# hr_subsystem.net
KiCad netlist of a schematic drawn in EAGLE
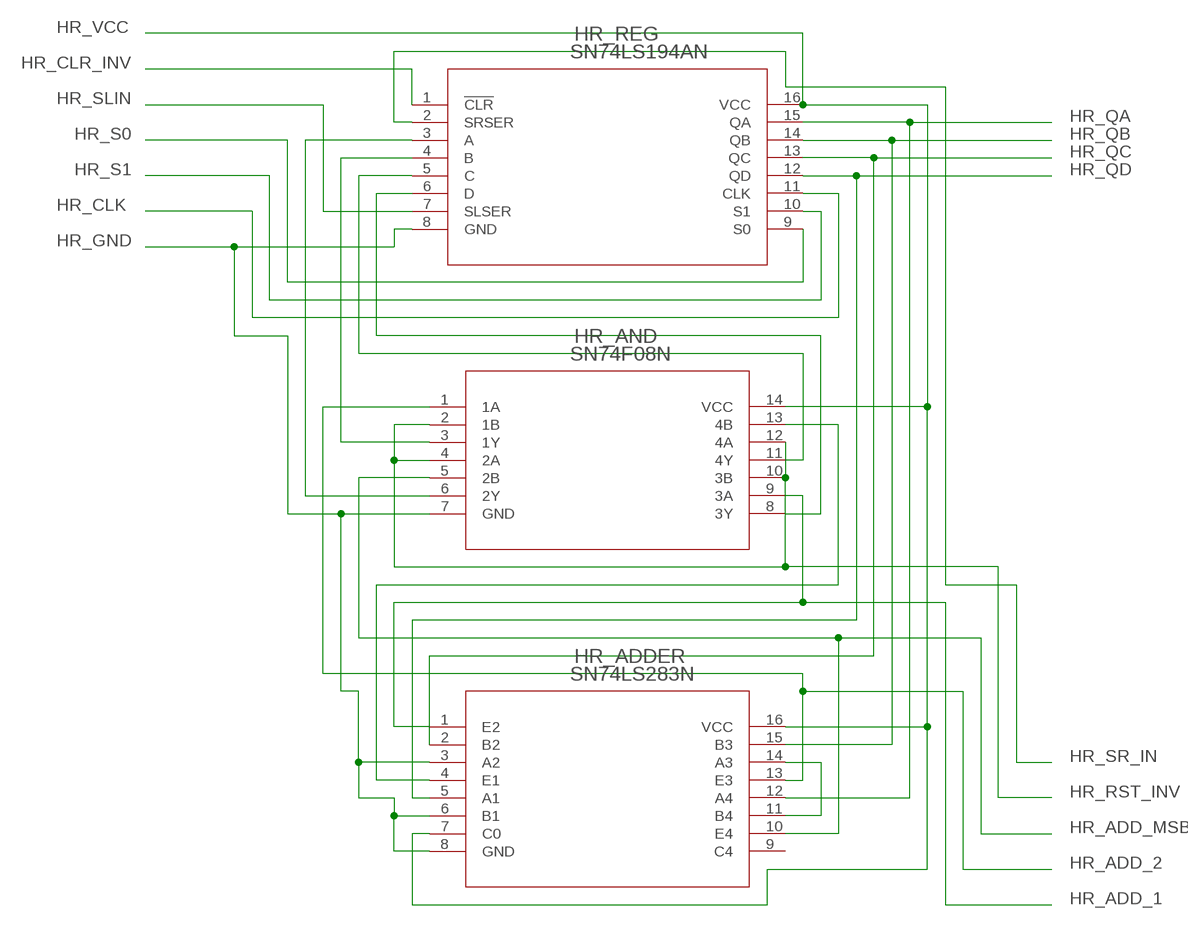
[diagram p0: schematic, sheet 1]

(export (version "E")
  (design (tool "Eeschema 10.0.6"))
  (components
    (comp (ref "HR_ADDER")
      (value "SN74LS283N")
      (footprint "eagle-import:N16")
      (fields
        (field (name "GENERIC_PART_NUMBER") "SN74LS283")
        (field (name "MANUFACTURER") "Texas Instruments")
      )
      (libsource (lib "eagle-import") (part "SN74LS283N"))
    )
    (comp (ref "HR_AND")
      (value "SN74F08N")
      (footprint "eagle-import:N14")
      (fields
        (field (name "GENERIC_PART_NUMBER") "SN74F08")
        (field (name "MANUFACTURER") "Texas Instruments")
      )
      (libsource (lib "eagle-import") (part "SN74F08N"))
    )
    (comp (ref "HR_REG")
      (value "SN74LS194AN")
      (footprint "eagle-import:N16")
      (fields
        (field (name "GENERIC_PART_NUMBER") "SN74LS194A")
        (field (name "MANUFACTURER") "Texas Instruments")
      )
      (libsource (lib "eagle-import") (part "SN74LS194AN"))
    )
  )
  (nets
    (net (code "1") (name "/HR_ADD_1") (class "Default")
      (node (ref "HR_ADDER") (pin "1") (pinfunction "E2_1") (pintype "output"))
      (node (ref "HR_AND") (pin "9") (pinfunction "3A_9") (pintype "input"))
    )
    (net (code "2") (name "/HR_ADD_2") (class "Default")
      (node (ref "HR_ADDER") (pin "13") (pinfunction "E3_13") (pintype "output"))
      (node (ref "HR_AND") (pin "1") (pinfunction "1A_1") (pintype "input"))
    )
    (net (code "3") (name "/HR_ADD_MSB") (class "Default")
      (node (ref "HR_ADDER") (pin "10") (pinfunction "E4_10") (pintype "output"))
      (node (ref "HR_AND") (pin "5") (pinfunction "2B_5") (pintype "input"))
    )
    (net (code "4") (name "/HR_CLK") (class "Default")
      (node (ref "HR_REG") (pin "11") (pinfunction "CLK_11") (pintype "input"))
    )
    (net (code "5") (name "/HR_CLR_INV") (class "Default")
      (node (ref "HR_REG") (pin "1") (pinfunction "~{CLR}_1") (pintype "input"))
    )
    (net (code "6") (name "/HR_GND") (class "Default")
      (node (ref "HR_ADDER") (pin "3") (pinfunction "A2_3") (pintype "input"))
      (node (ref "HR_ADDER") (pin "6") (pinfunction "B1_6") (pintype "input"))
      (node (ref "HR_ADDER") (pin "8") (pinfunction "GND_8") (pintype "power_in"))
      (node (ref "HR_AND") (pin "7") (pinfunction "GND_7") (pintype "power_in"))
      (node (ref "HR_REG") (pin "8") (pinfunction "GND_8") (pintype "power_in"))
    )
    (net (code "7") (name "/HR_QA") (class "Default")
      (node (ref "HR_ADDER") (pin "12") (pinfunction "A4_12") (pintype "input"))
      (node (ref "HR_REG") (pin "15") (pinfunction "QA_15") (pintype "output"))
    )
    (net (code "8") (name "/HR_QB") (class "Default")
      (node (ref "HR_ADDER") (pin "15") (pinfunction "B3_15") (pintype "input"))
      (node (ref "HR_REG") (pin "14") (pinfunction "QB_14") (pintype "output"))
    )
    (net (code "9") (name "/HR_QC") (class "Default")
      (node (ref "HR_ADDER") (pin "2") (pinfunction "B2_2") (pintype "input"))
      (node (ref "HR_REG") (pin "13") (pinfunction "QC_13") (pintype "output"))
    )
    (net (code "10") (name "/HR_QD") (class "Default")
      (node (ref "HR_ADDER") (pin "5") (pinfunction "A1_5") (pintype "input"))
      (node (ref "HR_REG") (pin "12") (pinfunction "QD_12") (pintype "output"))
    )
    (net (code "11") (name "/HR_RST_INV") (class "Default")
      (node (ref "HR_AND") (pin "10") (pinfunction "3B_10") (pintype "input"))
      (node (ref "HR_AND") (pin "12") (pinfunction "4A_12") (pintype "input"))
      (node (ref "HR_AND") (pin "2") (pinfunction "1B_2") (pintype "input"))
      (node (ref "HR_AND") (pin "4") (pinfunction "2A_4") (pintype "input"))
    )
    (net (code "12") (name "/HR_S0") (class "Default")
      (node (ref "HR_REG") (pin "9") (pinfunction "S0_9") (pintype "input"))
    )
    (net (code "13") (name "/HR_S1") (class "Default")
      (node (ref "HR_REG") (pin "10") (pinfunction "S1_10") (pintype "input"))
    )
    (net (code "14") (name "/HR_SLIN") (class "Default")
      (node (ref "HR_REG") (pin "7") (pinfunction "SLSER_7") (pintype "input"))
    )
    (net (code "15") (name "/HR_SR_IN") (class "Default")
      (node (ref "HR_REG") (pin "2") (pinfunction "SRSER_2") (pintype "input"))
    )
    (net (code "16") (name "/HR_VCC") (class "Default")
      (node (ref "HR_ADDER") (pin "16") (pinfunction "VCC_16") (pintype "power_in"))
      (node (ref "HR_ADDER") (pin "7") (pinfunction "C0_7") (pintype "input"))
      (node (ref "HR_AND") (pin "14") (pinfunction "VCC_14") (pintype "power_in"))
      (node (ref "HR_REG") (pin "16") (pinfunction "VCC_16") (pintype "power_in"))
    )
    (net (code "17") (name "Net-(HR_ADDER-A3)") (class "Default")
      (node (ref "HR_ADDER") (pin "11") (pinfunction "B4_11") (pintype "input"))
      (node (ref "HR_ADDER") (pin "14") (pinfunction "A3_14") (pintype "input"))
    )
    (net (code "18") (name "Net-(HR_ADDER-E1)") (class "Default")
      (node (ref "HR_ADDER") (pin "4") (pinfunction "E1_4") (pintype "output"))
      (node (ref "HR_AND") (pin "13") (pinfunction "4B_13") (pintype "input"))
    )
    (net (code "19") (name "Net-(HR_AND-1Y)") (class "Default")
      (node (ref "HR_AND") (pin "3") (pinfunction "1Y_3") (pintype "output"))
      (node (ref "HR_REG") (pin "4") (pinfunction "B_4") (pintype "input"))
    )
    (net (code "20") (name "Net-(HR_AND-2Y)") (class "Default")
      (node (ref "HR_AND") (pin "6") (pinfunction "2Y_6") (pintype "output"))
      (node (ref "HR_REG") (pin "3") (pinfunction "A_3") (pintype "input"))
    )
    (net (code "21") (name "Net-(HR_AND-3Y)") (class "Default")
      (node (ref "HR_AND") (pin "8") (pinfunction "3Y_8") (pintype "output"))
      (node (ref "HR_REG") (pin "6") (pinfunction "D_6") (pintype "input"))
    )
    (net (code "22") (name "Net-(HR_AND-4Y)") (class "Default")
      (node (ref "HR_AND") (pin "11") (pinfunction "4Y_11") (pintype "output"))
      (node (ref "HR_REG") (pin "5") (pinfunction "C_5") (pintype "input"))
    )
    (net (code "23") (name "unconnected-(HR_ADDER-C4-Pad9)") (class "Default")
      (node (ref "HR_ADDER") (pin "9") (pinfunction "C4_9") (pintype "input"))
    )
  )
)
